# Nixies.net
KiCad netlist of a schematic drawn in Altium Designer
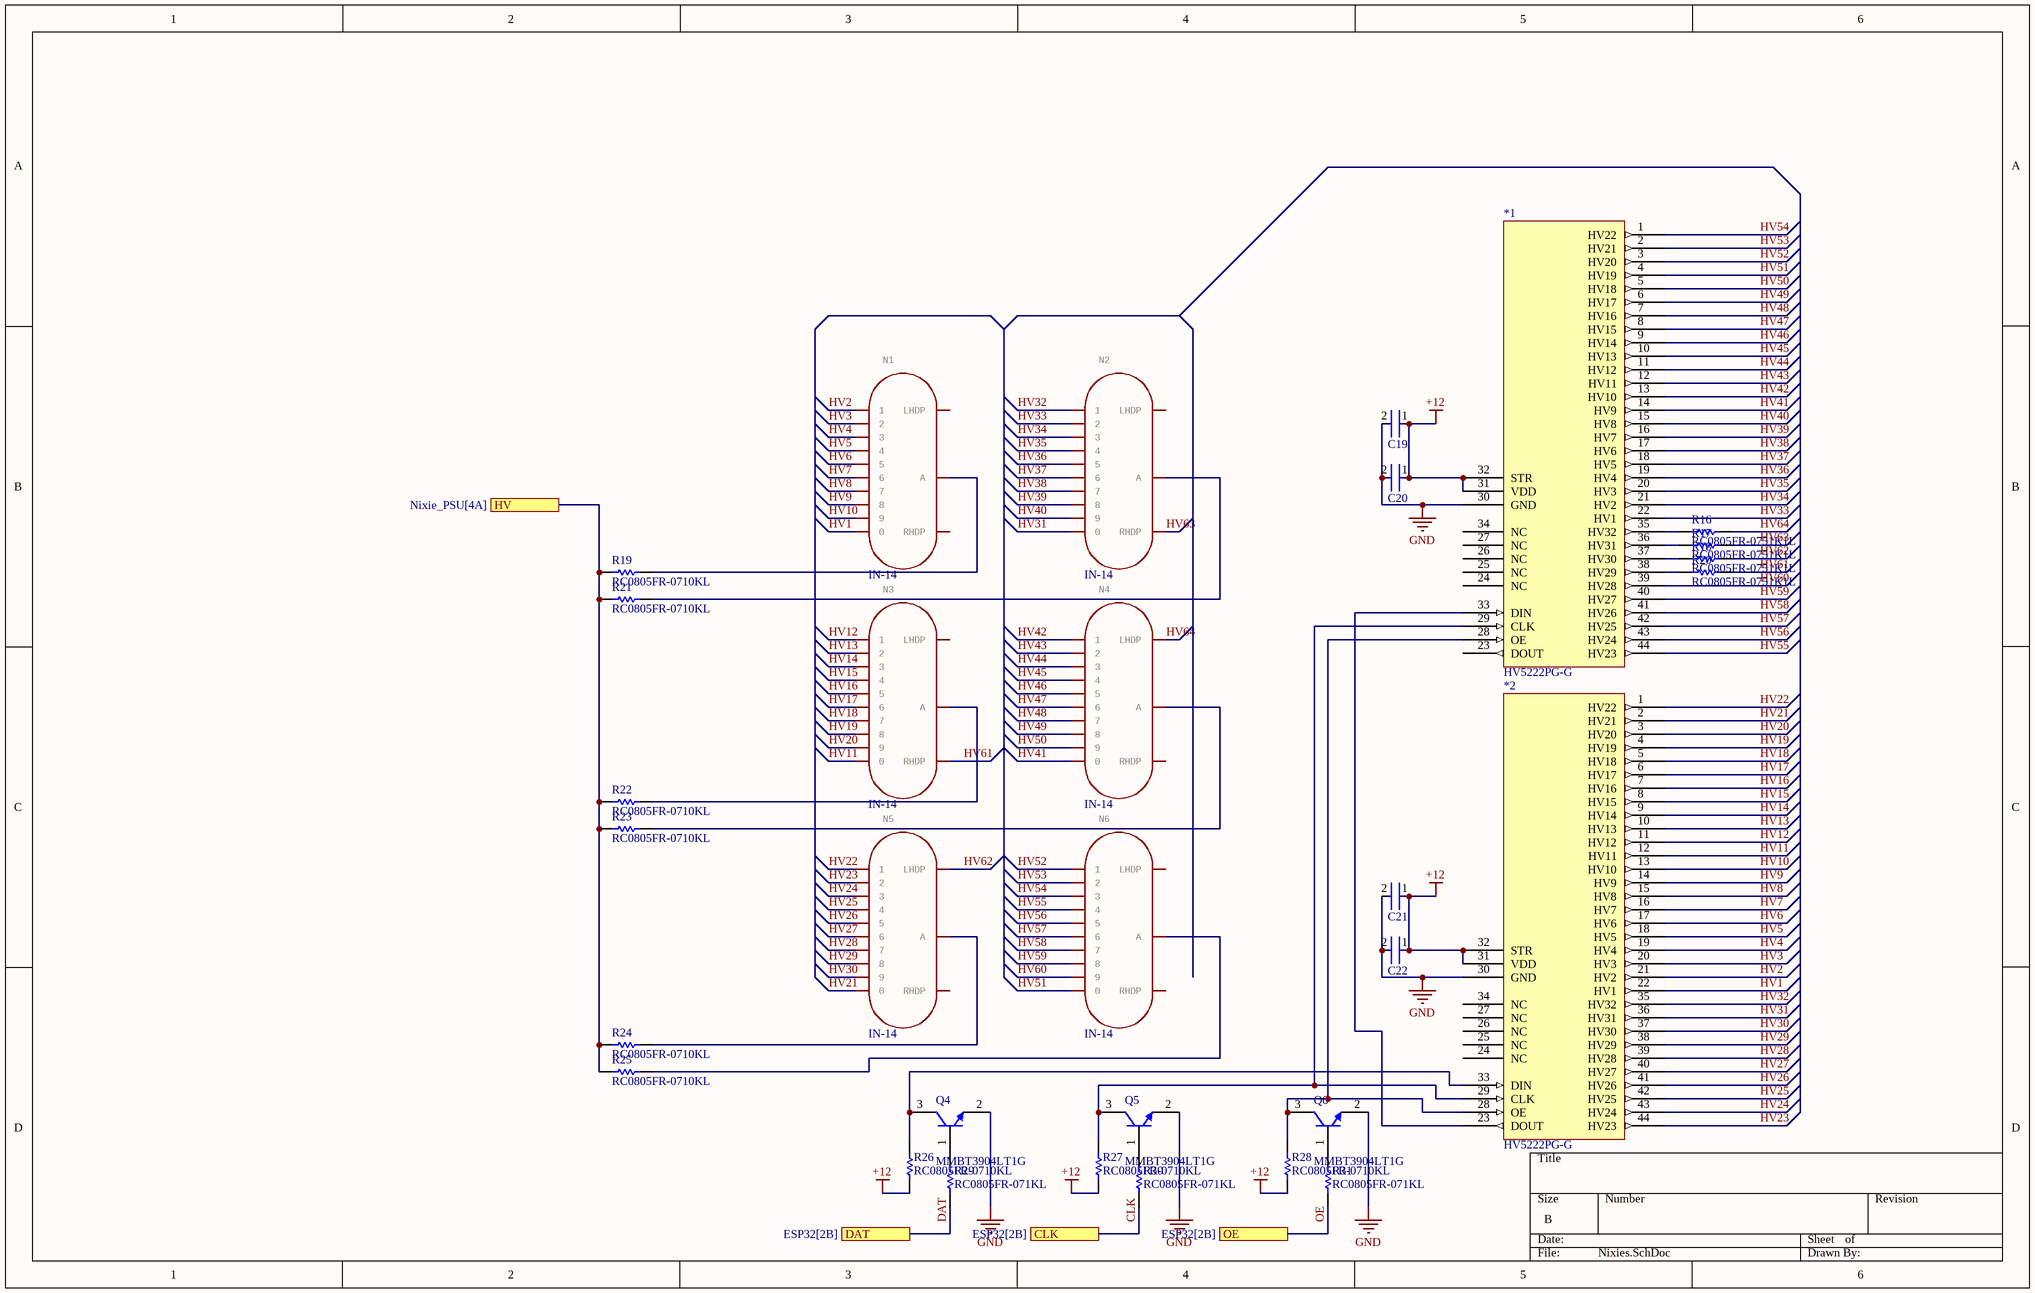
[diagram p0: Nixies.SchDoc]

(export (version "E")
  (design (tool "Eeschema 10.0.6"))
  (components
    (comp (ref "*1")
      (value "HV5222PG-G")
      (footprint "QFP80P1390X1390X235-44N")
      (description "EL Driver, 32-Segment, PQFP44")
      (libsource (lib "Purdue University") (part "HV5222PG-G-Symbol-1"))
    )
    (comp (ref "*2")
      (value "HV5222PG-G")
      (footprint "QFP80P1390X1390X235-44N")
      (description "EL Driver, 32-Segment, PQFP44")
      (libsource (lib "Purdue University") (part "HV5222PG-G-Symbol-1"))
    )
    (comp (ref "C19")
      (value "GRM188R60J476ME15D")
      (footprint "FP-GRM188-0_2-IPC_B")
      (description "Chip Multilayer Ceramic Capacitors for General Purpose, 0603, 47uF, X5R, 15%, 20%, 6.3V")
      (fields (field (name "TOLERANCE") "20%"))
      (libsource (lib "Altium Content Vault") (part "11868f565c42a9108669ba33697ecf6"))
    )
    (comp (ref "C20")
      (value "GRM188R60J476ME15D")
      (footprint "FP-GRM188-0_2-IPC_B")
      (description "Chip Multilayer Ceramic Capacitors for General Purpose, 0603, 47uF, X5R, 15%, 20%, 6.3V")
      (fields (field (name "TOLERANCE") "20%"))
      (libsource (lib "Altium Content Vault") (part "11868f565c42a9108669ba33697ecf6"))
    )
    (comp (ref "C21")
      (value "GRM188R60J476ME15D")
      (footprint "FP-GRM188-0_2-IPC_B")
      (description "Chip Multilayer Ceramic Capacitors for General Purpose, 0603, 47uF, X5R, 15%, 20%, 6.3V")
      (fields (field (name "TOLERANCE") "20%"))
      (libsource (lib "Altium Content Vault") (part "11868f565c42a9108669ba33697ecf6"))
    )
    (comp (ref "C22")
      (value "GRM188R60J476ME15D")
      (footprint "FP-GRM188-0_2-IPC_B")
      (description "Chip Multilayer Ceramic Capacitors for General Purpose, 0603, 47uF, X5R, 15%, 20%, 6.3V")
      (fields (field (name "TOLERANCE") "20%"))
      (libsource (lib "Altium Content Vault") (part "11868f565c42a9108669ba33697ecf6"))
    )
    (comp (ref "N1") (value "IN-14") (footprint "IN-14") (libsource (lib "Purdue University") (part "IN-14")))
    (comp (ref "N2") (value "IN-14") (footprint "IN-14") (libsource (lib "Purdue University") (part "IN-14")))
    (comp (ref "N3") (value "IN-14") (footprint "IN-14") (libsource (lib "Purdue University") (part "IN-14")))
    (comp (ref "N4") (value "IN-14") (footprint "IN-14") (libsource (lib "Purdue University") (part "IN-14")))
    (comp (ref "N5") (value "IN-14") (footprint "IN-14") (libsource (lib "Purdue University") (part "IN-14")))
    (comp (ref "N6") (value "IN-14") (footprint "IN-14") (libsource (lib "Purdue University") (part "IN-14")))
    (comp (ref "Q4")
      (value "MMBT3904LT1G")
      (footprint "ONSC-SOT-23-3-318-08_V")
      (description "General Purpose Transistor, NPN Silicon, 3-Pin SOT-23, Pb-Free, Tape and Reel")
      (fields (field (name "MANUFACTURER") "On Semiconductor"))
      (libsource (lib "Altium Content Vault") (part "ONSC-NPN-B1E2C3-3"))
    )
    (comp (ref "Q5")
      (value "MMBT3904LT1G")
      (footprint "ONSC-SOT-23-3-318-08_V")
      (description "General Purpose Transistor, NPN Silicon, 3-Pin SOT-23, Pb-Free, Tape and Reel")
      (fields (field (name "MANUFACTURER") "On Semiconductor"))
      (libsource (lib "Altium Content Vault") (part "ONSC-NPN-B1E2C3-3"))
    )
    (comp (ref "Q6")
      (value "MMBT3904LT1G")
      (footprint "ONSC-SOT-23-3-318-08_V")
      (description "General Purpose Transistor, NPN Silicon, 3-Pin SOT-23, Pb-Free, Tape and Reel")
      (fields (field (name "MANUFACTURER") "On Semiconductor"))
      (libsource (lib "Altium Content Vault") (part "ONSC-NPN-B1E2C3-3"))
    )
    (comp (ref "R16")
      (value "RC0805FR-0751K1L")
      (footprint "RESC2013X60X35LL10T20")
      (fields (field (name "MANUFACTURER") "Yageo"))
      (libsource (lib "Altium Content Vault") (part "RES"))
    )
    (comp (ref "R17")
      (value "RC0805FR-0751K1L")
      (footprint "RESC2013X60X35LL10T20")
      (fields (field (name "MANUFACTURER") "Yageo"))
      (libsource (lib "Altium Content Vault") (part "RES"))
    )
    (comp (ref "R18")
      (value "RC0805FR-0751K1L")
      (footprint "RESC2013X60X35LL10T20")
      (fields (field (name "MANUFACTURER") "Yageo"))
      (libsource (lib "Altium Content Vault") (part "RES"))
    )
    (comp (ref "R19")
      (value "RC0805FR-0710KL")
      (footprint "RESC2013X60X35NL10T20")
      (description "Chip Resistor, 10 KOhm, +/- 1%, 0.125 W, -55 to 155 degC, 0805 (2012 Metric), RoHS, Tape and Reel")
      (fields (field (name "MANUFACTURER") "Yageo"))
      (libsource (lib "Altium Content Vault") (part "RES-2"))
    )
    (comp (ref "R20")
      (value "RC0805FR-0751K1L")
      (footprint "RESC2013X60X35LL10T20")
      (fields (field (name "MANUFACTURER") "Yageo"))
      (libsource (lib "Altium Content Vault") (part "RES"))
    )
    (comp (ref "R21")
      (value "RC0805FR-0710KL")
      (footprint "RESC2013X60X35NL10T20")
      (description "Chip Resistor, 10 KOhm, +/- 1%, 0.125 W, -55 to 155 degC, 0805 (2012 Metric), RoHS, Tape and Reel")
      (fields (field (name "MANUFACTURER") "Yageo"))
      (libsource (lib "Altium Content Vault") (part "RES-2"))
    )
    (comp (ref "R22")
      (value "RC0805FR-0710KL")
      (footprint "RESC2013X60X35NL10T20")
      (description "Chip Resistor, 10 KOhm, +/- 1%, 0.125 W, -55 to 155 degC, 0805 (2012 Metric), RoHS, Tape and Reel")
      (fields (field (name "MANUFACTURER") "Yageo"))
      (libsource (lib "Altium Content Vault") (part "RES-2"))
    )
    (comp (ref "R23")
      (value "RC0805FR-0710KL")
      (footprint "RESC2013X60X35NL10T20")
      (description "Chip Resistor, 10 KOhm, +/- 1%, 0.125 W, -55 to 155 degC, 0805 (2012 Metric), RoHS, Tape and Reel")
      (fields (field (name "MANUFACTURER") "Yageo"))
      (libsource (lib "Altium Content Vault") (part "RES-2"))
    )
    (comp (ref "R24")
      (value "RC0805FR-0710KL")
      (footprint "RESC2013X60X35NL10T20")
      (description "Chip Resistor, 10 KOhm, +/- 1%, 0.125 W, -55 to 155 degC, 0805 (2012 Metric), RoHS, Tape and Reel")
      (fields (field (name "MANUFACTURER") "Yageo"))
      (libsource (lib "Altium Content Vault") (part "RES-2"))
    )
    (comp (ref "R25")
      (value "RC0805FR-0710KL")
      (footprint "RESC2013X60X35NL10T20")
      (description "Chip Resistor, 10 KOhm, +/- 1%, 0.125 W, -55 to 155 degC, 0805 (2012 Metric), RoHS, Tape and Reel")
      (fields (field (name "MANUFACTURER") "Yageo"))
      (libsource (lib "Altium Content Vault") (part "RES-2"))
    )
    (comp (ref "R26")
      (value "RC0805FR-0710KL")
      (footprint "RESC2013X60X35NL10T20")
      (description "Chip Resistor, 10 KOhm, +/- 1%, 0.125 W, -55 to 155 degC, 0805 (2012 Metric), RoHS, Tape and Reel")
      (fields (field (name "MANUFACTURER") "Yageo"))
      (libsource (lib "Altium Content Vault") (part "RES-2"))
    )
    (comp (ref "R27")
      (value "RC0805FR-0710KL")
      (footprint "RESC2013X60X35NL10T20")
      (description "Chip Resistor, 10 KOhm, +/- 1%, 0.125 W, -55 to 155 degC, 0805 (2012 Metric), RoHS, Tape and Reel")
      (fields (field (name "MANUFACTURER") "Yageo"))
      (libsource (lib "Altium Content Vault") (part "RES-2"))
    )
    (comp (ref "R28")
      (value "RC0805FR-0710KL")
      (footprint "RESC2013X60X35NL10T20")
      (description "Chip Resistor, 10 KOhm, +/- 1%, 0.125 W, -55 to 155 degC, 0805 (2012 Metric), RoHS, Tape and Reel")
      (fields (field (name "MANUFACTURER") "Yageo"))
      (libsource (lib "Altium Content Vault") (part "RES-2"))
    )
    (comp (ref "R29")
      (value "RC0805FR-071KL")
      (footprint "RESC2013X60X35ML10T20")
      (description "Chip Resistor, 1 KOhm, +/- 1%, 125 mW, -55 to 155 degC, 0805 (2012 Metric), RoHS, Tape and Reel")
      (fields (field (name "TOLERANCE") "1%") (field (name "MANUFACTURER") "Yageo"))
      (libsource (lib "Altium Content Vault") (part "RES-2"))
    )
    (comp (ref "R30")
      (value "RC0805FR-071KL")
      (footprint "RESC2013X60X35ML10T20")
      (description "Chip Resistor, 1 KOhm, +/- 1%, 125 mW, -55 to 155 degC, 0805 (2012 Metric), RoHS, Tape and Reel")
      (fields (field (name "TOLERANCE") "1%") (field (name "MANUFACTURER") "Yageo"))
      (libsource (lib "Altium Content Vault") (part "RES-2"))
    )
    (comp (ref "R31")
      (value "RC0805FR-071KL")
      (footprint "RESC2013X60X35ML10T20")
      (description "Chip Resistor, 1 KOhm, +/- 1%, 125 mW, -55 to 155 degC, 0805 (2012 Metric), RoHS, Tape and Reel")
      (fields (field (name "TOLERANCE") "1%") (field (name "MANUFACTURER") "Yageo"))
      (libsource (lib "Altium Content Vault") (part "RES-2"))
    )
  )
  (nets
    (net (code "1") (name "+12") (class "Default")
      (node (ref "*1") (pin "31") (pinfunction "VDD_31") (pintype "power_in"))
      (node (ref "*1") (pin "32") (pinfunction "STR_32") (pintype "power_in"))
      (node (ref "*2") (pin "31") (pinfunction "VDD_31") (pintype "power_in"))
      (node (ref "*2") (pin "32") (pinfunction "STR_32") (pintype "power_in"))
      (node (ref "C19") (pin "1") (pinfunction "1_1") (pintype "passive"))
      (node (ref "C20") (pin "1") (pinfunction "1_1") (pintype "passive"))
      (node (ref "C21") (pin "1") (pinfunction "1_1") (pintype "passive"))
      (node (ref "C22") (pin "1") (pinfunction "1_1") (pintype "passive"))
      (node (ref "R26") (pin "1") (pinfunction "1_1") (pintype "passive"))
      (node (ref "R27") (pin "1") (pinfunction "1_1") (pintype "passive"))
      (node (ref "R28") (pin "1") (pinfunction "1_1") (pintype "passive"))
    )
    (net (code "2") (name "/CLK") (class "Default")
      (node (ref "R30") (pin "1") (pinfunction "1_1") (pintype "passive"))
    )
    (net (code "3") (name "/DAT") (class "Default")
      (node (ref "R29") (pin "1") (pinfunction "1_1") (pintype "passive"))
    )
    (net (code "4") (name "/HV") (class "Default")
      (node (ref "R19") (pin "2") (pinfunction "2_2") (pintype "passive"))
      (node (ref "R21") (pin "2") (pinfunction "2_2") (pintype "passive"))
      (node (ref "R22") (pin "2") (pinfunction "2_2") (pintype "passive"))
      (node (ref "R23") (pin "2") (pinfunction "2_2") (pintype "passive"))
      (node (ref "R24") (pin "2") (pinfunction "2_2") (pintype "passive"))
      (node (ref "R25") (pin "2") (pinfunction "2_2") (pintype "passive"))
    )
    (net (code "5") (name "/HV1") (class "Default")
      (node (ref "*2") (pin "22") (pinfunction "HV1_22") (pintype "output"))
      (node (ref "N1") (pin "0") (pinfunction "0_0") (pintype "bidirectional"))
    )
    (net (code "6") (name "/HV2") (class "Default")
      (node (ref "*2") (pin "21") (pinfunction "HV2_21") (pintype "output"))
      (node (ref "N1") (pin "1") (pinfunction "1_1") (pintype "bidirectional"))
    )
    (net (code "7") (name "/HV3") (class "Default")
      (node (ref "*2") (pin "20") (pinfunction "HV3_20") (pintype "output"))
      (node (ref "N1") (pin "2") (pinfunction "2_2") (pintype "bidirectional"))
    )
    (net (code "8") (name "/HV4") (class "Default")
      (node (ref "*2") (pin "19") (pinfunction "HV4_19") (pintype "output"))
      (node (ref "N1") (pin "3") (pinfunction "3_3") (pintype "bidirectional"))
    )
    (net (code "9") (name "/HV5") (class "Default")
      (node (ref "*2") (pin "18") (pinfunction "HV5_18") (pintype "output"))
      (node (ref "N1") (pin "4") (pinfunction "4_4") (pintype "bidirectional"))
    )
    (net (code "10") (name "/HV6") (class "Default")
      (node (ref "*2") (pin "17") (pinfunction "HV6_17") (pintype "output"))
      (node (ref "N1") (pin "5") (pinfunction "5_5") (pintype "bidirectional"))
    )
    (net (code "11") (name "/HV7") (class "Default")
      (node (ref "*2") (pin "16") (pinfunction "HV7_16") (pintype "output"))
      (node (ref "N1") (pin "6") (pinfunction "6_6") (pintype "bidirectional"))
    )
    (net (code "12") (name "/HV8") (class "Default")
      (node (ref "*2") (pin "15") (pinfunction "HV8_15") (pintype "output"))
      (node (ref "N1") (pin "7") (pinfunction "7_7") (pintype "bidirectional"))
    )
    (net (code "13") (name "/HV9") (class "Default")
      (node (ref "*2") (pin "14") (pinfunction "HV9_14") (pintype "output"))
      (node (ref "N1") (pin "8") (pinfunction "8_8") (pintype "bidirectional"))
    )
    (net (code "14") (name "/HV10") (class "Default")
      (node (ref "*2") (pin "13") (pinfunction "HV10_13") (pintype "output"))
      (node (ref "N1") (pin "9") (pinfunction "9_9") (pintype "bidirectional"))
    )
    (net (code "15") (name "/HV11") (class "Default")
      (node (ref "*2") (pin "12") (pinfunction "HV11_12") (pintype "output"))
      (node (ref "N3") (pin "0") (pinfunction "0_0") (pintype "bidirectional"))
    )
    (net (code "16") (name "/HV12") (class "Default")
      (node (ref "*2") (pin "11") (pinfunction "HV12_11") (pintype "output"))
      (node (ref "N3") (pin "1") (pinfunction "1_1") (pintype "bidirectional"))
    )
    (net (code "17") (name "/HV13") (class "Default")
      (node (ref "*2") (pin "10") (pinfunction "HV13_10") (pintype "output"))
      (node (ref "N3") (pin "2") (pinfunction "2_2") (pintype "bidirectional"))
    )
    (net (code "18") (name "/HV14") (class "Default")
      (node (ref "*2") (pin "9") (pinfunction "HV14_9") (pintype "output"))
      (node (ref "N3") (pin "3") (pinfunction "3_3") (pintype "bidirectional"))
    )
    (net (code "19") (name "/HV15") (class "Default")
      (node (ref "*2") (pin "8") (pinfunction "HV15_8") (pintype "output"))
      (node (ref "N3") (pin "4") (pinfunction "4_4") (pintype "bidirectional"))
    )
    (net (code "20") (name "/HV16") (class "Default")
      (node (ref "*2") (pin "7") (pinfunction "HV16_7") (pintype "output"))
      (node (ref "N3") (pin "5") (pinfunction "5_5") (pintype "bidirectional"))
    )
    (net (code "21") (name "/HV17") (class "Default")
      (node (ref "*2") (pin "6") (pinfunction "HV17_6") (pintype "output"))
      (node (ref "N3") (pin "6") (pinfunction "6_6") (pintype "bidirectional"))
    )
    (net (code "22") (name "/HV18") (class "Default")
      (node (ref "*2") (pin "5") (pinfunction "HV18_5") (pintype "output"))
      (node (ref "N3") (pin "7") (pinfunction "7_7") (pintype "bidirectional"))
    )
    (net (code "23") (name "/HV19") (class "Default")
      (node (ref "*2") (pin "4") (pinfunction "HV19_4") (pintype "output"))
      (node (ref "N3") (pin "8") (pinfunction "8_8") (pintype "bidirectional"))
    )
    (net (code "24") (name "/HV20") (class "Default")
      (node (ref "*2") (pin "3") (pinfunction "HV20_3") (pintype "output"))
      (node (ref "N3") (pin "9") (pinfunction "9_9") (pintype "bidirectional"))
    )
    (net (code "25") (name "/HV21") (class "Default")
      (node (ref "*2") (pin "2") (pinfunction "HV21_2") (pintype "output"))
      (node (ref "N5") (pin "0") (pinfunction "0_0") (pintype "bidirectional"))
    )
    (net (code "26") (name "/HV22") (class "Default")
      (node (ref "*2") (pin "1") (pinfunction "HV22_1") (pintype "output"))
      (node (ref "N5") (pin "1") (pinfunction "1_1") (pintype "bidirectional"))
    )
    (net (code "27") (name "/HV23") (class "Default")
      (node (ref "*2") (pin "44") (pinfunction "HV23_44") (pintype "output"))
      (node (ref "N5") (pin "2") (pinfunction "2_2") (pintype "bidirectional"))
    )
    (net (code "28") (name "/HV24") (class "Default")
      (node (ref "*2") (pin "43") (pinfunction "HV24_43") (pintype "output"))
      (node (ref "N5") (pin "3") (pinfunction "3_3") (pintype "bidirectional"))
    )
    (net (code "29") (name "/HV25") (class "Default")
      (node (ref "*2") (pin "42") (pinfunction "HV25_42") (pintype "output"))
      (node (ref "N5") (pin "4") (pinfunction "4_4") (pintype "bidirectional"))
    )
    (net (code "30") (name "/HV26") (class "Default")
      (node (ref "*2") (pin "41") (pinfunction "HV26_41") (pintype "output"))
      (node (ref "N5") (pin "5") (pinfunction "5_5") (pintype "bidirectional"))
    )
    (net (code "31") (name "/HV27") (class "Default")
      (node (ref "*2") (pin "40") (pinfunction "HV27_40") (pintype "output"))
      (node (ref "N5") (pin "6") (pinfunction "6_6") (pintype "bidirectional"))
    )
    (net (code "32") (name "/HV28") (class "Default")
      (node (ref "*2") (pin "39") (pinfunction "HV28_39") (pintype "output"))
      (node (ref "N5") (pin "7") (pinfunction "7_7") (pintype "bidirectional"))
    )
    (net (code "33") (name "/HV29") (class "Default")
      (node (ref "*2") (pin "38") (pinfunction "HV29_38") (pintype "output"))
      (node (ref "N5") (pin "8") (pinfunction "8_8") (pintype "bidirectional"))
    )
    (net (code "34") (name "/HV30") (class "Default")
      (node (ref "*2") (pin "37") (pinfunction "HV30_37") (pintype "output"))
      (node (ref "N5") (pin "9") (pinfunction "9_9") (pintype "bidirectional"))
    )
    (net (code "35") (name "/HV31") (class "Default")
      (node (ref "*2") (pin "36") (pinfunction "HV31_36") (pintype "output"))
      (node (ref "N2") (pin "0") (pinfunction "0_0") (pintype "bidirectional"))
    )
    (net (code "36") (name "/HV32") (class "Default")
      (node (ref "*2") (pin "35") (pinfunction "HV32_35") (pintype "output"))
      (node (ref "N2") (pin "1") (pinfunction "1_1") (pintype "bidirectional"))
    )
    (net (code "37") (name "/HV33") (class "Default")
      (node (ref "*1") (pin "22") (pinfunction "HV1_22") (pintype "output"))
      (node (ref "N2") (pin "2") (pinfunction "2_2") (pintype "bidirectional"))
    )
    (net (code "38") (name "/HV34") (class "Default")
      (node (ref "*1") (pin "21") (pinfunction "HV2_21") (pintype "output"))
      (node (ref "N2") (pin "3") (pinfunction "3_3") (pintype "bidirectional"))
    )
    (net (code "39") (name "/HV35") (class "Default")
      (node (ref "*1") (pin "20") (pinfunction "HV3_20") (pintype "output"))
      (node (ref "N2") (pin "4") (pinfunction "4_4") (pintype "bidirectional"))
    )
    (net (code "40") (name "/HV36") (class "Default")
      (node (ref "*1") (pin "19") (pinfunction "HV4_19") (pintype "output"))
      (node (ref "N2") (pin "5") (pinfunction "5_5") (pintype "bidirectional"))
    )
    (net (code "41") (name "/HV37") (class "Default")
      (node (ref "*1") (pin "18") (pinfunction "HV5_18") (pintype "output"))
      (node (ref "N2") (pin "6") (pinfunction "6_6") (pintype "bidirectional"))
    )
    (net (code "42") (name "/HV38") (class "Default")
      (node (ref "*1") (pin "17") (pinfunction "HV6_17") (pintype "output"))
      (node (ref "N2") (pin "7") (pinfunction "7_7") (pintype "bidirectional"))
    )
    (net (code "43") (name "/HV39") (class "Default")
      (node (ref "*1") (pin "16") (pinfunction "HV7_16") (pintype "output"))
      (node (ref "N2") (pin "8") (pinfunction "8_8") (pintype "bidirectional"))
    )
    (net (code "44") (name "/HV40") (class "Default")
      (node (ref "*1") (pin "15") (pinfunction "HV8_15") (pintype "output"))
      (node (ref "N2") (pin "9") (pinfunction "9_9") (pintype "bidirectional"))
    )
    (net (code "45") (name "/HV41") (class "Default")
      (node (ref "*1") (pin "14") (pinfunction "HV9_14") (pintype "output"))
      (node (ref "N4") (pin "0") (pinfunction "0_0") (pintype "bidirectional"))
    )
    (net (code "46") (name "/HV42") (class "Default")
      (node (ref "*1") (pin "13") (pinfunction "HV10_13") (pintype "output"))
      (node (ref "N4") (pin "1") (pinfunction "1_1") (pintype "bidirectional"))
    )
    (net (code "47") (name "/HV43") (class "Default")
      (node (ref "*1") (pin "12") (pinfunction "HV11_12") (pintype "output"))
      (node (ref "N4") (pin "2") (pinfunction "2_2") (pintype "bidirectional"))
    )
    (net (code "48") (name "/HV44") (class "Default")
      (node (ref "*1") (pin "11") (pinfunction "HV12_11") (pintype "output"))
      (node (ref "N4") (pin "3") (pinfunction "3_3") (pintype "bidirectional"))
    )
    (net (code "49") (name "/HV45") (class "Default")
      (node (ref "*1") (pin "10") (pinfunction "HV13_10") (pintype "output"))
      (node (ref "N4") (pin "4") (pinfunction "4_4") (pintype "bidirectional"))
    )
    (net (code "50") (name "/HV46") (class "Default")
      (node (ref "*1") (pin "9") (pinfunction "HV14_9") (pintype "output"))
      (node (ref "N4") (pin "5") (pinfunction "5_5") (pintype "bidirectional"))
    )
    (net (code "51") (name "/HV47") (class "Default")
      (node (ref "*1") (pin "8") (pinfunction "HV15_8") (pintype "output"))
      (node (ref "N4") (pin "6") (pinfunction "6_6") (pintype "bidirectional"))
    )
    (net (code "52") (name "/HV48") (class "Default")
      (node (ref "*1") (pin "7") (pinfunction "HV16_7") (pintype "output"))
      (node (ref "N4") (pin "7") (pinfunction "7_7") (pintype "bidirectional"))
    )
    (net (code "53") (name "/HV49") (class "Default")
      (node (ref "*1") (pin "6") (pinfunction "HV17_6") (pintype "output"))
      (node (ref "N4") (pin "8") (pinfunction "8_8") (pintype "bidirectional"))
    )
    (net (code "54") (name "/HV50") (class "Default")
      (node (ref "*1") (pin "5") (pinfunction "HV18_5") (pintype "output"))
      (node (ref "N4") (pin "9") (pinfunction "9_9") (pintype "bidirectional"))
    )
    (net (code "55") (name "/HV51") (class "Default")
      (node (ref "*1") (pin "4") (pinfunction "HV19_4") (pintype "output"))
      (node (ref "N6") (pin "0") (pinfunction "0_0") (pintype "bidirectional"))
    )
    (net (code "56") (name "/HV52") (class "Default")
      (node (ref "*1") (pin "3") (pinfunction "HV20_3") (pintype "output"))
      (node (ref "N6") (pin "1") (pinfunction "1_1") (pintype "bidirectional"))
    )
    (net (code "57") (name "/HV53") (class "Default")
      (node (ref "*1") (pin "2") (pinfunction "HV21_2") (pintype "output"))
      (node (ref "N6") (pin "2") (pinfunction "2_2") (pintype "bidirectional"))
    )
    (net (code "58") (name "/HV54") (class "Default")
      (node (ref "*1") (pin "1") (pinfunction "HV22_1") (pintype "output"))
      (node (ref "N6") (pin "3") (pinfunction "3_3") (pintype "bidirectional"))
    )
    (net (code "59") (name "/HV55") (class "Default")
      (node (ref "*1") (pin "44") (pinfunction "HV23_44") (pintype "output"))
      (node (ref "N6") (pin "4") (pinfunction "4_4") (pintype "bidirectional"))
    )
    (net (code "60") (name "/HV56") (class "Default")
      (node (ref "*1") (pin "43") (pinfunction "HV24_43") (pintype "output"))
      (node (ref "N6") (pin "5") (pinfunction "5_5") (pintype "bidirectional"))
    )
    (net (code "61") (name "/HV57") (class "Default")
      (node (ref "*1") (pin "42") (pinfunction "HV25_42") (pintype "output"))
      (node (ref "N6") (pin "6") (pinfunction "6_6") (pintype "bidirectional"))
    )
    (net (code "62") (name "/HV58") (class "Default")
      (node (ref "*1") (pin "41") (pinfunction "HV26_41") (pintype "output"))
      (node (ref "N6") (pin "7") (pinfunction "7_7") (pintype "bidirectional"))
    )
    (net (code "63") (name "/HV59") (class "Default")
      (node (ref "*1") (pin "40") (pinfunction "HV27_40") (pintype "output"))
      (node (ref "N6") (pin "8") (pinfunction "8_8") (pintype "bidirectional"))
    )
    (net (code "64") (name "/HV60") (class "Default")
      (node (ref "*1") (pin "39") (pinfunction "HV28_39") (pintype "output"))
      (node (ref "N6") (pin "9") (pinfunction "9_9") (pintype "bidirectional"))
    )
    (net (code "65") (name "/HV61") (class "Default")
      (node (ref "N3") (pin "RHDP") (pinfunction "RHDP_RHDP") (pintype "bidirectional"))
      (node (ref "R20") (pin "2") (pinfunction "2_2") (pintype "passive"))
    )
    (net (code "66") (name "/HV62") (class "Default")
      (node (ref "N5") (pin "LHDP") (pinfunction "LHDP_LHDP") (pintype "bidirectional"))
      (node (ref "R18") (pin "2") (pinfunction "2_2") (pintype "passive"))
    )
    (net (code "67") (name "/HV63") (class "Default")
      (node (ref "N2") (pin "RHDP") (pinfunction "RHDP_RHDP") (pintype "bidirectional"))
      (node (ref "R17") (pin "2") (pinfunction "2_2") (pintype "passive"))
    )
    (net (code "68") (name "/HV64") (class "Default")
      (node (ref "N4") (pin "LHDP") (pinfunction "LHDP_LHDP") (pintype "bidirectional"))
      (node (ref "R16") (pin "2") (pinfunction "2_2") (pintype "passive"))
    )
    (net (code "69") (name "/OE") (class "Default")
      (node (ref "R31") (pin "1") (pinfunction "1_1") (pintype "passive"))
    )
    (net (code "70") (name "GND") (class "Default")
      (node (ref "*1") (pin "30") (pinfunction "GND_30") (pintype "power_in"))
      (node (ref "*2") (pin "30") (pinfunction "GND_30") (pintype "power_in"))
      (node (ref "C19") (pin "2") (pinfunction "2_2") (pintype "passive"))
      (node (ref "C20") (pin "2") (pinfunction "2_2") (pintype "passive"))
      (node (ref "C21") (pin "2") (pinfunction "2_2") (pintype "passive"))
      (node (ref "C22") (pin "2") (pinfunction "2_2") (pintype "passive"))
      (node (ref "Q4") (pin "2") (pinfunction "E_2") (pintype "passive"))
      (node (ref "Q5") (pin "2") (pinfunction "E_2") (pintype "passive"))
      (node (ref "Q6") (pin "2") (pinfunction "E_2") (pintype "passive"))
    )
    (net (code "71") (name "Net-(*1-CLK)") (class "Default")
      (node (ref "*1") (pin "29") (pinfunction "CLK_29") (pintype "input"))
      (node (ref "*2") (pin "29") (pinfunction "CLK_29") (pintype "input"))
      (node (ref "Q5") (pin "3") (pinfunction "C_3") (pintype "passive"))
      (node (ref "R27") (pin "2") (pinfunction "2_2") (pintype "passive"))
    )
    (net (code "72") (name "Net-(*1-DIN)") (class "Default")
      (node (ref "*1") (pin "33") (pinfunction "DIN_33") (pintype "input"))
      (node (ref "*2") (pin "23") (pinfunction "DOUT_23") (pintype "output"))
    )
    (net (code "73") (name "Net-(*1-HV29)") (class "Default")
      (node (ref "*1") (pin "38") (pinfunction "HV29_38") (pintype "output"))
      (node (ref "R20") (pin "1") (pinfunction "1_1") (pintype "passive"))
    )
    (net (code "74") (name "Net-(*1-HV30)") (class "Default")
      (node (ref "*1") (pin "37") (pinfunction "HV30_37") (pintype "output"))
      (node (ref "R18") (pin "1") (pinfunction "1_1") (pintype "passive"))
    )
    (net (code "75") (name "Net-(*1-HV31)") (class "Default")
      (node (ref "*1") (pin "36") (pinfunction "HV31_36") (pintype "output"))
      (node (ref "R17") (pin "1") (pinfunction "1_1") (pintype "passive"))
    )
    (net (code "76") (name "Net-(*1-HV32)") (class "Default")
      (node (ref "*1") (pin "35") (pinfunction "HV32_35") (pintype "output"))
      (node (ref "R16") (pin "1") (pinfunction "1_1") (pintype "passive"))
    )
    (net (code "77") (name "Net-(*1-OE)") (class "Default")
      (node (ref "*1") (pin "28") (pinfunction "OE_28") (pintype "input"))
      (node (ref "*2") (pin "28") (pinfunction "OE_28") (pintype "input"))
      (node (ref "Q6") (pin "3") (pinfunction "C_3") (pintype "passive"))
      (node (ref "R28") (pin "2") (pinfunction "2_2") (pintype "passive"))
    )
    (net (code "78") (name "Net-(*2-DIN)") (class "Default")
      (node (ref "*2") (pin "33") (pinfunction "DIN_33") (pintype "input"))
      (node (ref "Q4") (pin "3") (pinfunction "C_3") (pintype "passive"))
      (node (ref "R26") (pin "2") (pinfunction "2_2") (pintype "passive"))
    )
    (net (code "79") (name "Net-(N1-PadA)") (class "Default")
      (node (ref "N1") (pin "A") (pinfunction "A_A") (pintype "bidirectional"))
      (node (ref "R19") (pin "1") (pinfunction "1_1") (pintype "passive"))
    )
    (net (code "80") (name "Net-(N2-PadA)") (class "Default")
      (node (ref "N2") (pin "A") (pinfunction "A_A") (pintype "bidirectional"))
      (node (ref "R21") (pin "1") (pinfunction "1_1") (pintype "passive"))
    )
    (net (code "81") (name "Net-(N3-PadA)") (class "Default")
      (node (ref "N3") (pin "A") (pinfunction "A_A") (pintype "bidirectional"))
      (node (ref "R22") (pin "1") (pinfunction "1_1") (pintype "passive"))
    )
    (net (code "82") (name "Net-(N4-PadA)") (class "Default")
      (node (ref "N4") (pin "A") (pinfunction "A_A") (pintype "bidirectional"))
      (node (ref "R23") (pin "1") (pinfunction "1_1") (pintype "passive"))
    )
    (net (code "83") (name "Net-(N5-PadA)") (class "Default")
      (node (ref "N5") (pin "A") (pinfunction "A_A") (pintype "bidirectional"))
      (node (ref "R24") (pin "1") (pinfunction "1_1") (pintype "passive"))
    )
    (net (code "84") (name "Net-(N6-PadA)") (class "Default")
      (node (ref "N6") (pin "A") (pinfunction "A_A") (pintype "bidirectional"))
      (node (ref "R25") (pin "1") (pinfunction "1_1") (pintype "passive"))
    )
    (net (code "85") (name "Net-(Q4-B)") (class "Default")
      (node (ref "Q4") (pin "1") (pinfunction "B_1") (pintype "passive"))
      (node (ref "R29") (pin "2") (pinfunction "2_2") (pintype "passive"))
    )
    (net (code "86") (name "Net-(Q5-B)") (class "Default")
      (node (ref "Q5") (pin "1") (pinfunction "B_1") (pintype "passive"))
      (node (ref "R30") (pin "2") (pinfunction "2_2") (pintype "passive"))
    )
    (net (code "87") (name "Net-(Q6-B)") (class "Default")
      (node (ref "Q6") (pin "1") (pinfunction "B_1") (pintype "passive"))
      (node (ref "R31") (pin "2") (pinfunction "2_2") (pintype "passive"))
    )
    (net (code "88") (name "unconnected-(*1-DOUT-Pad23)") (class "Default")
      (node (ref "*1") (pin "23") (pinfunction "DOUT_23") (pintype "output"))
    )
    (net (code "89") (name "unconnected-(*1-NC-Pad24)") (class "Default")
      (node (ref "*1") (pin "24") (pinfunction "NC_24") (pintype "passive"))
    )
    (net (code "90") (name "unconnected-(*1-NC-Pad25)") (class "Default")
      (node (ref "*1") (pin "25") (pinfunction "NC_25") (pintype "passive"))
    )
    (net (code "91") (name "unconnected-(*1-NC-Pad26)") (class "Default")
      (node (ref "*1") (pin "26") (pinfunction "NC_26") (pintype "passive"))
    )
    (net (code "92") (name "unconnected-(*1-NC-Pad27)") (class "Default")
      (node (ref "*1") (pin "27") (pinfunction "NC_27") (pintype "passive"))
    )
    (net (code "93") (name "unconnected-(*1-NC-Pad34)") (class "Default")
      (node (ref "*1") (pin "34") (pinfunction "NC_34") (pintype "passive"))
    )
    (net (code "94") (name "unconnected-(*2-NC-Pad24)") (class "Default")
      (node (ref "*2") (pin "24") (pinfunction "NC_24") (pintype "passive"))
    )
    (net (code "95") (name "unconnected-(*2-NC-Pad25)") (class "Default")
      (node (ref "*2") (pin "25") (pinfunction "NC_25") (pintype "passive"))
    )
    (net (code "96") (name "unconnected-(*2-NC-Pad26)") (class "Default")
      (node (ref "*2") (pin "26") (pinfunction "NC_26") (pintype "passive"))
    )
    (net (code "97") (name "unconnected-(*2-NC-Pad27)") (class "Default")
      (node (ref "*2") (pin "27") (pinfunction "NC_27") (pintype "passive"))
    )
    (net (code "98") (name "unconnected-(*2-NC-Pad34)") (class "Default")
      (node (ref "*2") (pin "34") (pinfunction "NC_34") (pintype "passive"))
    )
    (net (code "99") (name "unconnected-(N1-PadLHDP)") (class "Default")
      (node (ref "N1") (pin "LHDP") (pinfunction "LHDP_LHDP") (pintype "bidirectional"))
    )
    (net (code "100") (name "unconnected-(N1-PadRHDP)") (class "Default")
      (node (ref "N1") (pin "RHDP") (pinfunction "RHDP_RHDP") (pintype "bidirectional"))
    )
    (net (code "101") (name "unconnected-(N2-PadLHDP)") (class "Default")
      (node (ref "N2") (pin "LHDP") (pinfunction "LHDP_LHDP") (pintype "bidirectional"))
    )
    (net (code "102") (name "unconnected-(N3-PadLHDP)") (class "Default")
      (node (ref "N3") (pin "LHDP") (pinfunction "LHDP_LHDP") (pintype "bidirectional"))
    )
    (net (code "103") (name "unconnected-(N4-PadRHDP)") (class "Default")
      (node (ref "N4") (pin "RHDP") (pinfunction "RHDP_RHDP") (pintype "bidirectional"))
    )
    (net (code "104") (name "unconnected-(N5-PadRHDP)") (class "Default")
      (node (ref "N5") (pin "RHDP") (pinfunction "RHDP_RHDP") (pintype "bidirectional"))
    )
    (net (code "105") (name "unconnected-(N6-PadLHDP)") (class "Default")
      (node (ref "N6") (pin "LHDP") (pinfunction "LHDP_LHDP") (pintype "bidirectional"))
    )
    (net (code "106") (name "unconnected-(N6-PadRHDP)") (class "Default")
      (node (ref "N6") (pin "RHDP") (pinfunction "RHDP_RHDP") (pintype "bidirectional"))
    )
  )
)
